# SIO2-dev.net
KiCad netlist of a schematic drawn in EAGLE
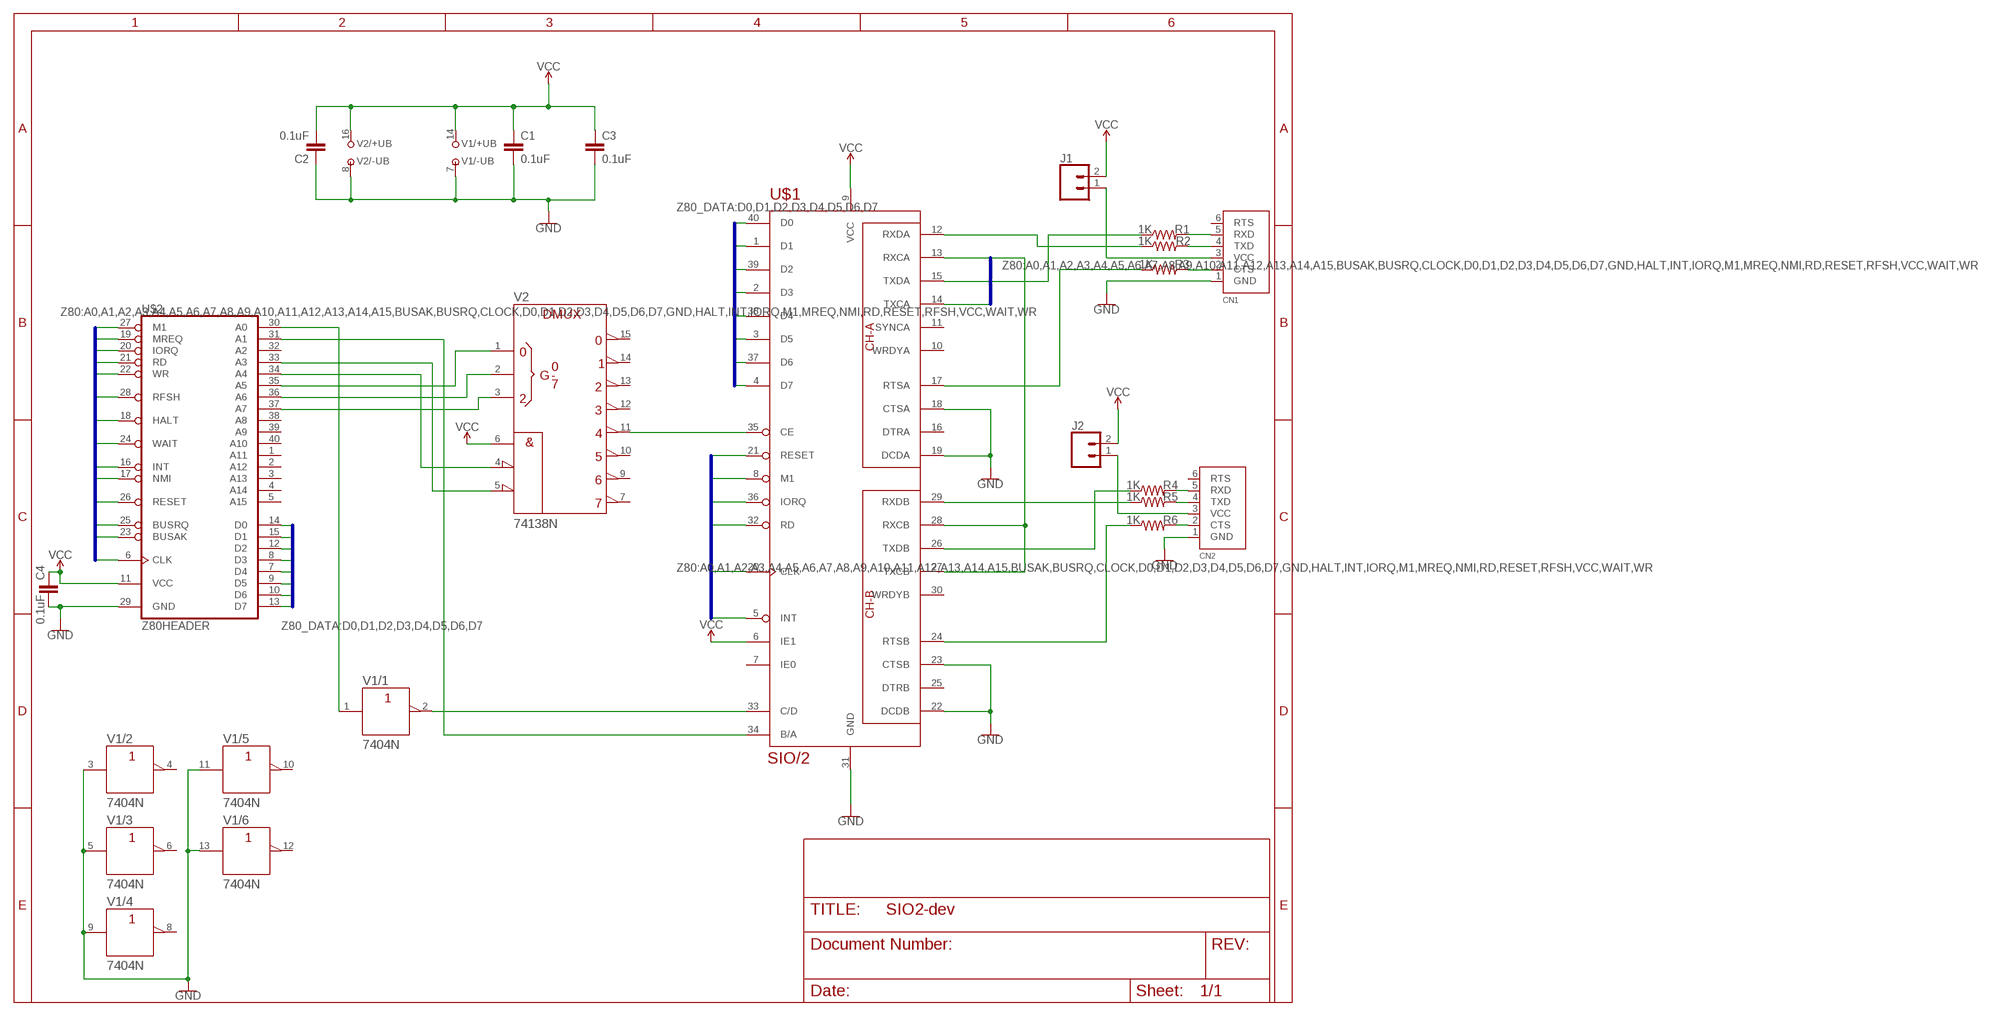
[diagram p0: schematic, sheet 1]

(export (version "E")
  (design (tool "Eeschema 10.0.6"))
  (components
    (comp (ref "C1")
      (value "0.1uF")
      (footprint "eagle-import:C2.5-3")
      (libsource (lib "eagle-import") (part "C2,5-3"))
    )
    (comp (ref "C2")
      (value "0.1uF")
      (footprint "eagle-import:C2.5-3")
      (libsource (lib "eagle-import") (part "C2,5-3"))
    )
    (comp (ref "C3")
      (value "0.1uF")
      (footprint "eagle-import:C2.5-3")
      (libsource (lib "eagle-import") (part "C2,5-3"))
    )
    (comp (ref "C4")
      (value "0.1uF")
      (footprint "eagle-import:C2.5-3")
      (libsource (lib "eagle-import") (part "C2,5-3"))
    )
    (comp (ref "CN1")
      (value "FTDIUSBCABLE")
      (footprint "eagle-import:1X06_ROUND")
      (libsource (lib "eagle-import") (part "FTDIUSBCABLE"))
    )
    (comp (ref "CN2")
      (value "FTDIUSBCABLE")
      (footprint "eagle-import:1X06_ROUND")
      (libsource (lib "eagle-import") (part "FTDIUSBCABLE"))
    )
    (comp (ref "J1")
      (value "CONN_02")
      (footprint "eagle-import:1X02")
      (libsource (lib "eagle-import") (part "CONN_02"))
    )
    (comp (ref "J2")
      (value "CONN_02")
      (footprint "eagle-import:1X02")
      (libsource (lib "eagle-import") (part "CONN_02"))
    )
    (comp (ref "R1")
      (value "1K")
      (footprint "eagle-import:AXIAL-0.3")
      (libsource (lib "eagle-import") (part "RESISTORAXIAL-0.3"))
    )
    (comp (ref "R2")
      (value "1K")
      (footprint "eagle-import:AXIAL-0.3")
      (libsource (lib "eagle-import") (part "RESISTORAXIAL-0.3"))
    )
    (comp (ref "R3")
      (value "1K")
      (footprint "eagle-import:AXIAL-0.3")
      (libsource (lib "eagle-import") (part "RESISTORAXIAL-0.3"))
    )
    (comp (ref "R4")
      (value "1K")
      (footprint "eagle-import:AXIAL-0.3")
      (libsource (lib "eagle-import") (part "RESISTORAXIAL-0.3"))
    )
    (comp (ref "R5")
      (value "1K")
      (footprint "eagle-import:AXIAL-0.3")
      (libsource (lib "eagle-import") (part "RESISTORAXIAL-0.3"))
    )
    (comp (ref "R6")
      (value "1K")
      (footprint "eagle-import:AXIAL-0.3")
      (libsource (lib "eagle-import") (part "RESISTORAXIAL-0.3"))
    )
    (comp (ref "U$1")
      (value "SIO/2")
      (footprint "eagle-import:DIL40")
      (libsource (lib "eagle-import") (part "SIO/2"))
    )
    (comp (ref "U$2")
      (value "Z80HEADER")
      (footprint "eagle-import:2X20")
      (libsource (lib "eagle-import") (part "Z80HEADER"))
    )
    (comp (ref "V1")
      (value "7404N")
      (footprint "eagle-import:DIL14")
      (libsource (lib "eagle-import") (part "7404N"))
    )
    (comp (ref "V2")
      (value "74138N")
      (footprint "eagle-import:DIL16")
      (libsource (lib "eagle-import") (part "74138N"))
    )
  )
  (nets
    (net (code "26") (name "/CLOCK") (class "Default")
      (node (ref "U$1") (pin "13") (pinfunction "RXCA_13") (pintype "bidirectional"))
      (node (ref "U$1") (pin "14") (pinfunction "TXCA_14") (pintype "bidirectional"))
      (node (ref "U$1") (pin "20") (pinfunction "CLK_20") (pintype "input"))
      (node (ref "U$1") (pin "27") (pinfunction "TXCB_27") (pintype "bidirectional"))
      (node (ref "U$1") (pin "28") (pinfunction "RXCB_28") (pintype "bidirectional"))
      (node (ref "U$2") (pin "6") (pinfunction "CLK_6") (pintype "input"))
    )
    (net (code "27") (name "/D0") (class "Default")
      (node (ref "U$1") (pin "40") (pinfunction "D0_40") (pintype "bidirectional"))
      (node (ref "U$2") (pin "14") (pinfunction "D0_14") (pintype "bidirectional"))
    )
    (net (code "28") (name "/D1") (class "Default")
      (node (ref "U$1") (pin "1") (pinfunction "D1_1") (pintype "bidirectional"))
      (node (ref "U$2") (pin "15") (pinfunction "D1_15") (pintype "bidirectional"))
    )
    (net (code "29") (name "/D2") (class "Default")
      (node (ref "U$1") (pin "39") (pinfunction "D2_39") (pintype "bidirectional"))
      (node (ref "U$2") (pin "12") (pinfunction "D2_12") (pintype "bidirectional"))
    )
    (net (code "30") (name "/D3") (class "Default")
      (node (ref "U$1") (pin "2") (pinfunction "D3_2") (pintype "bidirectional"))
      (node (ref "U$2") (pin "8") (pinfunction "D3_8") (pintype "bidirectional"))
    )
    (net (code "31") (name "/D4") (class "Default")
      (node (ref "U$1") (pin "38") (pinfunction "D4_38") (pintype "bidirectional"))
      (node (ref "U$2") (pin "7") (pinfunction "D4_7") (pintype "bidirectional"))
    )
    (net (code "32") (name "/D5") (class "Default")
      (node (ref "U$1") (pin "3") (pinfunction "D5_3") (pintype "bidirectional"))
      (node (ref "U$2") (pin "9") (pinfunction "D5_9") (pintype "bidirectional"))
    )
    (net (code "33") (name "/D6") (class "Default")
      (node (ref "U$1") (pin "37") (pinfunction "D6_37") (pintype "bidirectional"))
      (node (ref "U$2") (pin "10") (pinfunction "D6_10") (pintype "bidirectional"))
    )
    (net (code "34") (name "/D7") (class "Default")
      (node (ref "U$1") (pin "4") (pinfunction "D7_4") (pintype "bidirectional"))
      (node (ref "U$2") (pin "13") (pinfunction "D7_13") (pintype "bidirectional"))
    )
    (net (code "35") (name "/INT") (class "Default")
      (node (ref "U$1") (pin "5") (pinfunction "INT_5") (pintype "bidirectional"))
      (node (ref "U$2") (pin "16") (pinfunction "INT_16") (pintype "input"))
    )
    (net (code "36") (name "/IORQ") (class "Default")
      (node (ref "U$1") (pin "36") (pinfunction "IORQ_36") (pintype "input"))
      (node (ref "U$2") (pin "20") (pinfunction "IORQ_20") (pintype "output"))
    )
    (net (code "37") (name "/M1") (class "Default")
      (node (ref "U$1") (pin "8") (pinfunction "M1_8") (pintype "input"))
      (node (ref "U$2") (pin "27") (pinfunction "M1_27") (pintype "output"))
    )
    (net (code "38") (name "/RD") (class "Default")
      (node (ref "U$1") (pin "32") (pinfunction "RD_32") (pintype "input"))
      (node (ref "U$2") (pin "21") (pinfunction "RD_21") (pintype "output"))
    )
    (net (code "39") (name "/RESET") (class "Default")
      (node (ref "U$1") (pin "21") (pinfunction "RESET_21") (pintype "input"))
      (node (ref "U$2") (pin "26") (pinfunction "RESET_26") (pintype "input"))
    )
    (net (code "42") (name "GND") (class "Default")
      (node (ref "C1") (pin "2") (pinfunction "2_2") (pintype "passive"))
      (node (ref "C2") (pin "1") (pinfunction "1_1") (pintype "passive"))
      (node (ref "C3") (pin "2") (pinfunction "2_2") (pintype "passive"))
      (node (ref "C4") (pin "2") (pinfunction "2_2") (pintype "passive"))
      (node (ref "CN1") (pin "1") (pinfunction "GND_1") (pintype "bidirectional"))
      (node (ref "CN2") (pin "1") (pinfunction "GND_1") (pintype "bidirectional"))
      (node (ref "U$1") (pin "18") (pinfunction "CTSA_18") (pintype "bidirectional"))
      (node (ref "U$1") (pin "19") (pinfunction "DCDA_19") (pintype "bidirectional"))
      (node (ref "U$1") (pin "22") (pinfunction "DCDB_22") (pintype "bidirectional"))
      (node (ref "U$1") (pin "23") (pinfunction "CTSB_23") (pintype "bidirectional"))
      (node (ref "U$1") (pin "31") (pinfunction "GND_31") (pintype "power_in"))
      (node (ref "U$2") (pin "29") (pinfunction "GND_29") (pintype "power_in"))
      (node (ref "V1") (pin "11") (pinfunction "A_11") (pintype "input"))
      (node (ref "V1") (pin "13") (pinfunction "A_13") (pintype "input"))
      (node (ref "V1") (pin "3") (pinfunction "A_3") (pintype "input"))
      (node (ref "V1") (pin "5") (pinfunction "A_5") (pintype "input"))
      (node (ref "V1") (pin "7") (pinfunction "-UB_7") (pintype "power_in"))
      (node (ref "V1") (pin "9") (pinfunction "A_9") (pintype "input"))
      (node (ref "V2") (pin "8") (pinfunction "-UB_8") (pintype "power_in"))
    )
    (net (code "43") (name "Net-(CN1-CTS)") (class "Default")
      (node (ref "CN1") (pin "2") (pinfunction "CTS_2") (pintype "bidirectional"))
      (node (ref "R3") (pin "P$2") (pinfunction "2_P$2") (pintype "passive"))
    )
    (net (code "44") (name "Net-(CN1-RXD)") (class "Default")
      (node (ref "CN1") (pin "5") (pinfunction "RXD_5") (pintype "bidirectional"))
      (node (ref "R1") (pin "P$2") (pinfunction "2_P$2") (pintype "passive"))
    )
    (net (code "45") (name "Net-(CN1-TXD)") (class "Default")
      (node (ref "CN1") (pin "4") (pinfunction "TXD_4") (pintype "bidirectional"))
      (node (ref "R2") (pin "P$2") (pinfunction "2_P$2") (pintype "passive"))
    )
    (net (code "46") (name "Net-(CN1-VCC)") (class "Default")
      (node (ref "CN1") (pin "3") (pinfunction "VCC_3") (pintype "bidirectional"))
      (node (ref "J1") (pin "1") (pinfunction "1_1") (pintype "passive"))
    )
    (net (code "47") (name "Net-(CN2-CTS)") (class "Default")
      (node (ref "CN2") (pin "2") (pinfunction "CTS_2") (pintype "bidirectional"))
      (node (ref "R6") (pin "P$2") (pinfunction "2_P$2") (pintype "passive"))
    )
    (net (code "48") (name "Net-(CN2-RXD)") (class "Default")
      (node (ref "CN2") (pin "5") (pinfunction "RXD_5") (pintype "bidirectional"))
      (node (ref "R4") (pin "P$2") (pinfunction "2_P$2") (pintype "passive"))
    )
    (net (code "49") (name "Net-(CN2-TXD)") (class "Default")
      (node (ref "CN2") (pin "4") (pinfunction "TXD_4") (pintype "bidirectional"))
      (node (ref "R5") (pin "P$2") (pinfunction "2_P$2") (pintype "passive"))
    )
    (net (code "50") (name "Net-(CN2-VCC)") (class "Default")
      (node (ref "CN2") (pin "3") (pinfunction "VCC_3") (pintype "bidirectional"))
      (node (ref "J2") (pin "1") (pinfunction "1_1") (pintype "passive"))
    )
    (net (code "51") (name "Net-(R1-1)") (class "Default")
      (node (ref "R1") (pin "P$1") (pinfunction "1_P$1") (pintype "passive"))
      (node (ref "U$1") (pin "15") (pinfunction "TXDA_15") (pintype "bidirectional"))
    )
    (net (code "52") (name "Net-(R2-1)") (class "Default")
      (node (ref "R2") (pin "P$1") (pinfunction "1_P$1") (pintype "passive"))
      (node (ref "U$1") (pin "12") (pinfunction "RXDA_12") (pintype "bidirectional"))
    )
    (net (code "53") (name "Net-(R3-1)") (class "Default")
      (node (ref "R3") (pin "P$1") (pinfunction "1_P$1") (pintype "passive"))
      (node (ref "U$1") (pin "17") (pinfunction "RTSA_17") (pintype "bidirectional"))
    )
    (net (code "54") (name "Net-(R4-1)") (class "Default")
      (node (ref "R4") (pin "P$1") (pinfunction "1_P$1") (pintype "passive"))
      (node (ref "U$1") (pin "26") (pinfunction "TXDB_26") (pintype "bidirectional"))
    )
    (net (code "55") (name "Net-(R5-1)") (class "Default")
      (node (ref "R5") (pin "P$1") (pinfunction "1_P$1") (pintype "passive"))
      (node (ref "U$1") (pin "29") (pinfunction "RXDB_29") (pintype "bidirectional"))
    )
    (net (code "56") (name "Net-(R6-1)") (class "Default")
      (node (ref "R6") (pin "P$1") (pinfunction "1_P$1") (pintype "passive"))
      (node (ref "U$1") (pin "24") (pinfunction "RTSB_24") (pintype "bidirectional"))
    )
    (net (code "57") (name "Net-(U$1-B{slash}A)") (class "Default")
      (node (ref "U$1") (pin "34") (pinfunction "B/A_34") (pintype "bidirectional"))
      (node (ref "U$2") (pin "31") (pinfunction "A1_31") (pintype "output"))
    )
    (net (code "58") (name "Net-(U$1-CE)") (class "Default")
      (node (ref "U$1") (pin "35") (pinfunction "CE_35") (pintype "input"))
      (node (ref "V2") (pin "11") (pinfunction "Y4_11") (pintype "output"))
    )
    (net (code "59") (name "Net-(U$1-C{slash}D)") (class "Default")
      (node (ref "U$1") (pin "33") (pinfunction "C/D_33") (pintype "bidirectional"))
      (node (ref "V1") (pin "2") (pinfunction "Y_2") (pintype "output"))
    )
    (net (code "60") (name "Net-(U$2-A0)") (class "Default")
      (node (ref "U$2") (pin "30") (pinfunction "A0_30") (pintype "output"))
      (node (ref "V1") (pin "1") (pinfunction "A_1") (pintype "input"))
    )
    (net (code "61") (name "Net-(U$2-A3)") (class "Default")
      (node (ref "U$2") (pin "33") (pinfunction "A3_33") (pintype "output"))
      (node (ref "V2") (pin "5") (pinfunction "~{G2B}_5") (pintype "input"))
    )
    (net (code "62") (name "Net-(U$2-A4)") (class "Default")
      (node (ref "U$2") (pin "34") (pinfunction "A4_34") (pintype "output"))
      (node (ref "V2") (pin "4") (pinfunction "~{G2A}_4") (pintype "input"))
    )
    (net (code "63") (name "Net-(U$2-A5)") (class "Default")
      (node (ref "U$2") (pin "35") (pinfunction "A5_35") (pintype "output"))
      (node (ref "V2") (pin "1") (pinfunction "A_1") (pintype "input"))
    )
    (net (code "64") (name "Net-(U$2-A6)") (class "Default")
      (node (ref "U$2") (pin "36") (pinfunction "A6_36") (pintype "output"))
      (node (ref "V2") (pin "2") (pinfunction "B_2") (pintype "input"))
    )
    (net (code "65") (name "Net-(U$2-A7)") (class "Default")
      (node (ref "U$2") (pin "37") (pinfunction "A7_37") (pintype "output"))
      (node (ref "V2") (pin "3") (pinfunction "C_3") (pintype "input"))
    )
    (net (code "66") (name "VCC") (class "Default")
      (node (ref "C1") (pin "1") (pinfunction "1_1") (pintype "passive"))
      (node (ref "C2") (pin "2") (pinfunction "2_2") (pintype "passive"))
      (node (ref "C3") (pin "1") (pinfunction "1_1") (pintype "passive"))
      (node (ref "C4") (pin "1") (pinfunction "1_1") (pintype "passive"))
      (node (ref "J1") (pin "2") (pinfunction "2_2") (pintype "passive"))
      (node (ref "J2") (pin "2") (pinfunction "2_2") (pintype "passive"))
      (node (ref "U$1") (pin "6") (pinfunction "IE1_6") (pintype "bidirectional"))
      (node (ref "U$1") (pin "9") (pinfunction "VCC_9") (pintype "power_in"))
      (node (ref "U$2") (pin "11") (pinfunction "VCC_11") (pintype "power_in"))
      (node (ref "V1") (pin "14") (pinfunction "+UB_14") (pintype "power_in"))
      (node (ref "V2") (pin "16") (pinfunction "+UB_16") (pintype "power_in"))
      (node (ref "V2") (pin "6") (pinfunction "G1_6") (pintype "input"))
    )
    (net (code "67") (name "unconnected-(CN1-RTS-Pad6)") (class "Default")
      (node (ref "CN1") (pin "6") (pinfunction "RTS_6") (pintype "bidirectional"))
    )
    (net (code "68") (name "unconnected-(CN2-RTS-Pad6)") (class "Default")
      (node (ref "CN2") (pin "6") (pinfunction "RTS_6") (pintype "bidirectional"))
    )
    (net (code "69") (name "unconnected-(U$1-DTRA-Pad16)") (class "Default")
      (node (ref "U$1") (pin "16") (pinfunction "DTRA_16") (pintype "bidirectional"))
    )
    (net (code "70") (name "unconnected-(U$1-DTRB-Pad25)") (class "Default")
      (node (ref "U$1") (pin "25") (pinfunction "DTRB_25") (pintype "bidirectional"))
    )
    (net (code "71") (name "unconnected-(U$1-IE0-Pad7)") (class "Default")
      (node (ref "U$1") (pin "7") (pinfunction "IE0_7") (pintype "bidirectional"))
    )
    (net (code "72") (name "unconnected-(U$1-SYNCA-Pad11)") (class "Default")
      (node (ref "U$1") (pin "11") (pinfunction "SYNCA_11") (pintype "bidirectional"))
    )
    (net (code "73") (name "unconnected-(U$1-WRDYA-Pad10)") (class "Default")
      (node (ref "U$1") (pin "10") (pinfunction "WRDYA_10") (pintype "bidirectional"))
    )
    (net (code "74") (name "unconnected-(U$1-WRDYB-Pad30)") (class "Default")
      (node (ref "U$1") (pin "30") (pinfunction "WRDYB_30") (pintype "bidirectional"))
    )
    (net (code "75") (name "unconnected-(U$2-A2-Pad32)") (class "Default")
      (node (ref "U$2") (pin "32") (pinfunction "A2_32") (pintype "output"))
    )
    (net (code "76") (name "unconnected-(U$2-A8-Pad38)") (class "Default")
      (node (ref "U$2") (pin "38") (pinfunction "A8_38") (pintype "output"))
    )
    (net (code "77") (name "unconnected-(U$2-A9-Pad39)") (class "Default")
      (node (ref "U$2") (pin "39") (pinfunction "A9_39") (pintype "output"))
    )
    (net (code "78") (name "unconnected-(U$2-A10-Pad40)") (class "Default")
      (node (ref "U$2") (pin "40") (pinfunction "A10_40") (pintype "output"))
    )
    (net (code "79") (name "unconnected-(U$2-A11-Pad1)") (class "Default")
      (node (ref "U$2") (pin "1") (pinfunction "A11_1") (pintype "output"))
    )
    (net (code "80") (name "unconnected-(U$2-A12-Pad2)") (class "Default")
      (node (ref "U$2") (pin "2") (pinfunction "A12_2") (pintype "output"))
    )
    (net (code "81") (name "unconnected-(U$2-A13-Pad3)") (class "Default")
      (node (ref "U$2") (pin "3") (pinfunction "A13_3") (pintype "output"))
    )
    (net (code "82") (name "unconnected-(U$2-A14-Pad4)") (class "Default")
      (node (ref "U$2") (pin "4") (pinfunction "A14_4") (pintype "output"))
    )
    (net (code "83") (name "unconnected-(U$2-A15-Pad5)") (class "Default")
      (node (ref "U$2") (pin "5") (pinfunction "A15_5") (pintype "output"))
    )
    (net (code "84") (name "unconnected-(U$2-BUSAK-Pad23)") (class "Default")
      (node (ref "U$2") (pin "23") (pinfunction "BUSAK_23") (pintype "output"))
    )
    (net (code "85") (name "unconnected-(U$2-BUSRQ-Pad25)") (class "Default")
      (node (ref "U$2") (pin "25") (pinfunction "BUSRQ_25") (pintype "input"))
    )
    (net (code "86") (name "unconnected-(U$2-HALT-Pad18)") (class "Default")
      (node (ref "U$2") (pin "18") (pinfunction "HALT_18") (pintype "output"))
    )
    (net (code "87") (name "unconnected-(U$2-MREQ-Pad19)") (class "Default")
      (node (ref "U$2") (pin "19") (pinfunction "MREQ_19") (pintype "output"))
    )
    (net (code "88") (name "unconnected-(U$2-NMI-Pad17)") (class "Default")
      (node (ref "U$2") (pin "17") (pinfunction "NMI_17") (pintype "input"))
    )
    (net (code "89") (name "unconnected-(U$2-RFSH-Pad28)") (class "Default")
      (node (ref "U$2") (pin "28") (pinfunction "RFSH_28") (pintype "output"))
    )
    (net (code "90") (name "unconnected-(U$2-WAIT-Pad24)") (class "Default")
      (node (ref "U$2") (pin "24") (pinfunction "WAIT_24") (pintype "input"))
    )
    (net (code "91") (name "unconnected-(U$2-WR-Pad22)") (class "Default")
      (node (ref "U$2") (pin "22") (pinfunction "WR_22") (pintype "output"))
    )
    (net (code "92") (name "unconnected-(V1D-Y-Pad4)") (class "Default")
      (node (ref "V1") (pin "4") (pinfunction "Y_4") (pintype "output"))
    )
    (net (code "93") (name "unconnected-(V1E-Y-Pad6)") (class "Default")
      (node (ref "V1") (pin "6") (pinfunction "Y_6") (pintype "output"))
    )
    (net (code "94") (name "unconnected-(V1F-Y-Pad8)") (class "Default")
      (node (ref "V1") (pin "8") (pinfunction "Y_8") (pintype "output"))
    )
    (net (code "95") (name "unconnected-(V1G-Y-Pad10)") (class "Default")
      (node (ref "V1") (pin "10") (pinfunction "Y_10") (pintype "output"))
    )
    (net (code "96") (name "unconnected-(V1H-Y-Pad12)") (class "Default")
      (node (ref "V1") (pin "12") (pinfunction "Y_12") (pintype "output"))
    )
    (net (code "97") (name "unconnected-(V2C-Y0-Pad15)") (class "Default")
      (node (ref "V2") (pin "15") (pinfunction "Y0_15") (pintype "output"))
    )
    (net (code "98") (name "unconnected-(V2C-Y1-Pad14)") (class "Default")
      (node (ref "V2") (pin "14") (pinfunction "Y1_14") (pintype "output"))
    )
    (net (code "99") (name "unconnected-(V2C-Y2-Pad13)") (class "Default")
      (node (ref "V2") (pin "13") (pinfunction "Y2_13") (pintype "output"))
    )
    (net (code "100") (name "unconnected-(V2C-Y3-Pad12)") (class "Default")
      (node (ref "V2") (pin "12") (pinfunction "Y3_12") (pintype "output"))
    )
    (net (code "101") (name "unconnected-(V2C-Y5-Pad10)") (class "Default")
      (node (ref "V2") (pin "10") (pinfunction "Y5_10") (pintype "output"))
    )
    (net (code "102") (name "unconnected-(V2C-Y6-Pad9)") (class "Default")
      (node (ref "V2") (pin "9") (pinfunction "Y6_9") (pintype "output"))
    )
    (net (code "103") (name "unconnected-(V2C-Y7-Pad7)") (class "Default")
      (node (ref "V2") (pin "7") (pinfunction "Y7_7") (pintype "output"))
    )
  )
)
